# FanControl.net
KiCad netlist of a schematic drawn in Altium Designer
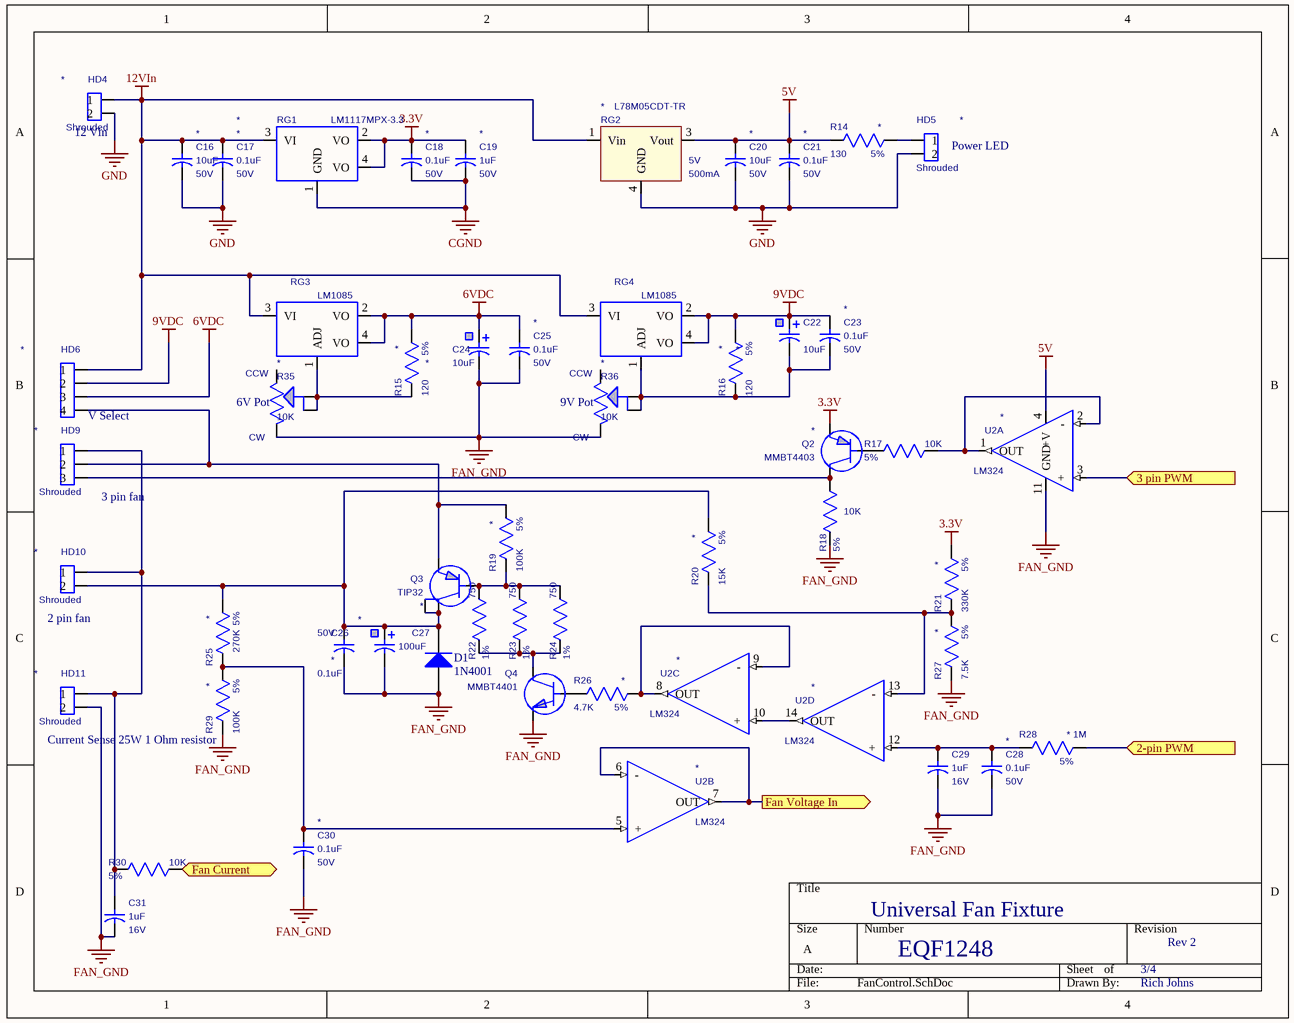
[diagram p0: FanControl.SchDoc]

(export (version "E")
  (design (tool "Eeschema 10.0.6"))
  (components
    (comp (ref "C16")
      (value "10uF")
      (footprint "1206")
      (fields
        (field (name "DNS") "*")
        (field (name "VOLTAGE") "50V")
        (field (name "TOLERANCE") "+/- 20%")
        (field (name "Comment") "CAP_NON_POLAR_SMT")
        (field (name "CHECKEDBY") "Sam Rhoufiry")
        (field (name "CREATEDBY") "Mike Tyger")
        (field (name "LASTUPDATEDBY") "Mike Tyger")
      )
      (libsource (lib "bome") (part "CAP_NON_POLAR_SMT"))
    )
    (comp (ref "C17")
      (value "0.1uF")
      (footprint "0603")
      (fields
        (field (name "DNS") "*")
        (field (name "VOLTAGE") "50V")
        (field (name "TOLERANCE") "+/- 20%")
        (field (name "Comment") "CAP_NON_POLAR_SMT")
        (field (name "CHECKEDBY") "Sam Rhoufiry")
        (field (name "CREATEDBY") "Mike Tyger")
        (field (name "LASTUPDATEDBY") "Mike Tyger")
      )
      (libsource (lib "bome") (part "CAP_NON_POLAR_SMT"))
    )
    (comp (ref "C18")
      (value "0.1uF")
      (footprint "0603")
      (fields
        (field (name "DNS") "*")
        (field (name "VOLTAGE") "50V")
        (field (name "TOLERANCE") "+/- 20%")
        (field (name "Comment") "CAP_NON_POLAR_SMT")
        (field (name "CHECKEDBY") "Sam Rhoufiry")
        (field (name "CREATEDBY") "Mike Tyger")
        (field (name "LASTUPDATEDBY") "Mike Tyger")
      )
      (libsource (lib "bome") (part "CAP_NON_POLAR_SMT"))
    )
    (comp (ref "C19")
      (value "1uF")
      (footprint "1812")
      (description "Capacitor, 1uF, 50V, Ceramic, Z5U, +/- 20%, Non-Polar, 1812, Kemet: C1812C105M5UACTU or equivalent")
      (fields
        (field (name "DNS") "*")
        (field (name "VOLTAGE") "50V")
        (field (name "TOLERANCE") "+/- 20%")
        (field (name "Comment") "CAP_NON_POLAR_SMT")
        (field (name "CHECKEDBY") "Sam Rhoufiry")
        (field (name "CREATEDBY") "Mike Tyger")
        (field (name "LASTUPDATEDBY") "Mike Tyger")
      )
      (libsource (lib "bome") (part "CAP_NON_POLAR_SMT"))
    )
    (comp (ref "C20")
      (value "10uF")
      (footprint "1206")
      (fields
        (field (name "DNS") "*")
        (field (name "VOLTAGE") "50V")
        (field (name "TOLERANCE") "+/- 20%")
        (field (name "Comment") "CAP_NON_POLAR_SMT")
        (field (name "CHECKEDBY") "Sam Rhoufiry")
        (field (name "CREATEDBY") "Mike Tyger")
        (field (name "LASTUPDATEDBY") "Mike Tyger")
      )
      (libsource (lib "bome") (part "CAP_NON_POLAR_SMT"))
    )
    (comp (ref "C21")
      (value "0.1uF")
      (footprint "0603")
      (fields
        (field (name "DNS") "*")
        (field (name "VOLTAGE") "50V")
        (field (name "TOLERANCE") "+/- 20%")
        (field (name "Comment") "CAP_NON_POLAR_SMT")
        (field (name "CHECKEDBY") "Sam Rhoufiry")
        (field (name "CREATEDBY") "Mike Tyger")
        (field (name "LASTUPDATEDBY") "Mike Tyger")
      )
      (libsource (lib "bome") (part "CAP_NON_POLAR_SMT"))
    )
    (comp (ref "C22")
      (value "10uF")
      (footprint "EIA3216-18")
      (fields
        (field (name "VOLTAGE") "16V")
        (field (name "TOLERANCE") "+/- 20%")
        (field (name "DNS") "*")
        (field (name "Comment") "10UF_TANT_16V")
        (field (name "CHECKEDBY") "B. Lyon")
      )
      (libsource (lib "bome") (part "10UF_TANT_16V"))
    )
    (comp (ref "C23")
      (value "0.1uF")
      (footprint "0603")
      (fields
        (field (name "DNS") "*")
        (field (name "VOLTAGE") "50V")
        (field (name "TOLERANCE") "+/- 20%")
        (field (name "Comment") "CAP_NON_POLAR_SMT")
        (field (name "CHECKEDBY") "Sam Rhoufiry")
        (field (name "CREATEDBY") "Mike Tyger")
        (field (name "LASTUPDATEDBY") "Mike Tyger")
      )
      (libsource (lib "bome") (part "CAP_NON_POLAR_SMT"))
    )
    (comp (ref "C24")
      (value "10uF")
      (footprint "EIA3216-18")
      (fields
        (field (name "VOLTAGE") "16V")
        (field (name "TOLERANCE") "+/- 20%")
        (field (name "DNS") "*")
        (field (name "Comment") "10UF_TANT_16V")
        (field (name "CHECKEDBY") "B. Lyon")
      )
      (libsource (lib "bome") (part "10UF_TANT_16V"))
    )
    (comp (ref "C25")
      (value "0.1uF")
      (footprint "0603")
      (fields
        (field (name "DNS") "*")
        (field (name "VOLTAGE") "50V")
        (field (name "TOLERANCE") "+/- 20%")
        (field (name "Comment") "CAP_NON_POLAR_SMT")
        (field (name "CHECKEDBY") "Sam Rhoufiry")
        (field (name "CREATEDBY") "Mike Tyger")
        (field (name "LASTUPDATEDBY") "Mike Tyger")
      )
      (libsource (lib "bome") (part "CAP_NON_POLAR_SMT"))
    )
    (comp (ref "C26")
      (value "100uF")
      (footprint "CAP_100RP42")
      (fields
        (field (name "DNS") "*")
        (field (name "VOLTAGE") "35V")
        (field (name "TOLERANCE") "+/- 20%")
        (field (name "Comment") "100UF_RP_35V_100")
        (field (name "CHECKEDBY") "A. Tyger")
      )
      (libsource (lib "bome") (part "100UF_RP_35V_100"))
    )
    (comp (ref "C27")
      (value "0.1uF")
      (footprint "0603")
      (fields
        (field (name "DNS") "*")
        (field (name "VOLTAGE") "50V")
        (field (name "TOLERANCE") "+/- 20%")
        (field (name "Comment") "CAP_NON_POLAR_SMT")
        (field (name "CHECKEDBY") "Sam Rhoufiry")
        (field (name "CREATEDBY") "Mike Tyger")
        (field (name "LASTUPDATEDBY") "Mike Tyger")
      )
      (libsource (lib "bome") (part "CAP_NON_POLAR_SMT"))
    )
    (comp (ref "C28")
      (value "0.1uF")
      (footprint "0603")
      (fields
        (field (name "DNS") "*")
        (field (name "VOLTAGE") "50V")
        (field (name "TOLERANCE") "+/- 20%")
        (field (name "Comment") "CAP_NON_POLAR_SMT")
        (field (name "CHECKEDBY") "Sam Rhoufiry")
        (field (name "CREATEDBY") "Mike Tyger")
        (field (name "LASTUPDATEDBY") "Mike Tyger")
      )
      (libsource (lib "bome") (part "CAP_NON_POLAR_SMT"))
    )
    (comp (ref "C29")
      (value "1uF")
      (footprint "0603")
      (fields
        (field (name "TOLERANCE") "+/- 10%")
        (field (name "VOLTAGE") "16V")
        (field (name "Comment") "1.0uF_0603_16V")
        (field (name "CHECKEDBY") "gdeguzman")
        (field (name "LASTUPDATEDBY") "Rui Zhang")
      )
      (libsource (lib "bome") (part "1.0uF_0603_16V"))
    )
    (comp (ref "C30")
      (value "0.1uF")
      (footprint "0603")
      (fields
        (field (name "DNS") "*")
        (field (name "VOLTAGE") "50V")
        (field (name "TOLERANCE") "+/- 20%")
        (field (name "Comment") "CAP_NON_POLAR_SMT")
        (field (name "CHECKEDBY") "Sam Rhoufiry")
        (field (name "CREATEDBY") "Mike Tyger")
        (field (name "LASTUPDATEDBY") "Mike Tyger")
      )
      (libsource (lib "bome") (part "CAP_NON_POLAR_SMT"))
    )
    (comp (ref "C31")
      (value "1uF")
      (footprint "0603")
      (fields
        (field (name "TOLERANCE") "+/- 10%")
        (field (name "VOLTAGE") "16V")
        (field (name "Comment") "1.0uF_0603_16V")
        (field (name "CHECKEDBY") "gdeguzman")
        (field (name "LASTUPDATEDBY") "Rui Zhang")
      )
      (libsource (lib "bome") (part "1.0uF_0603_16V"))
    )
    (comp (ref "D1")
      (value "1N4001")
      (footprint "DSO-C2/X3.3")
      (description "Default Diode")
      (fields (field (name "PUBLISHER") "Altium Limited"))
      (libsource (lib "Miscellaneous Devices") (part "Diode"))
    )
    (comp (ref "HD4")
      (value "HDR2PIN100SHRD")
      (footprint "HDR2PIN100SHRD")
      (description "Header, 0.100 in., 2 Pins, Shrouded, AMP: 644486-2")
      (fields
        (field (name "DNS") "*")
        (field (name "HEADERTYPE") "Shrouded")
        (field (name "CHECKEDBY") "*")
        (field (name "LASTUPDATEDBY") "Mike Tyger")
      )
      (libsource (lib "bome") (part "HDR2PIN100SHRD"))
    )
    (comp (ref "HD5")
      (value "HDR2PIN100SHRD")
      (footprint "HDR2PIN100SHRD")
      (description "Header, 0.100 in., 2 Pins, Shrouded, AMP: 644486-2")
      (fields
        (field (name "DNS") "*")
        (field (name "HEADERTYPE") "Shrouded")
        (field (name "CHECKEDBY") "*")
        (field (name "LASTUPDATEDBY") "Mike Tyger")
      )
      (libsource (lib "bome") (part "HDR2PIN100SHRD"))
    )
    (comp (ref "HD6")
      (value "HDR4PIN100SHRD")
      (footprint "HDR4PIN100SHRD")
      (description "Header, 0.100 in., 4 pin Pins, Shrouded, AMP: 644486-4")
      (fields (field (name "DNS") "*") (field (name "CHECKEDBY") "Michael Angeli"))
      (libsource (lib "bome") (part "HDR4PIN100SHRD"))
    )
    (comp (ref "HD9")
      (value "HDR3PIN100SHRD")
      (footprint "HDR3PIN100SHRD")
      (description "Header, 0.100 in., 3 pin Pins, Shrouded, AMP: 644486-3")
      (fields
        (field (name "DNS") "*")
        (field (name "HEADERTYPE") "Shrouded")
        (field (name "CHECKEDBY") "Grunt Mcfunkwhistle")
      )
      (libsource (lib "bome") (part "HDR3PIN100SHRD"))
    )
    (comp (ref "HD10")
      (value "HDR2PIN100SHRD")
      (footprint "HDR2PIN100SHRD")
      (description "Header, 0.100 in., 2 Pins, Shrouded, AMP: 644486-2")
      (fields
        (field (name "DNS") "*")
        (field (name "HEADERTYPE") "Shrouded")
        (field (name "CHECKEDBY") "*")
        (field (name "LASTUPDATEDBY") "Mike Tyger")
      )
      (libsource (lib "bome") (part "HDR2PIN100SHRD"))
    )
    (comp (ref "HD11")
      (value "HDR2PIN100SHRD")
      (footprint "HDR2PIN100SHRD")
      (description "Header, 0.100 in., 2 Pins, Shrouded, AMP: 644486-2")
      (fields
        (field (name "DNS") "*")
        (field (name "HEADERTYPE") "Shrouded")
        (field (name "CHECKEDBY") "*")
        (field (name "LASTUPDATEDBY") "Mike Tyger")
      )
      (libsource (lib "bome") (part "HDR2PIN100SHRD"))
    )
    (comp (ref "Q2")
      (value "MMBT4403")
      (footprint "SOT23-3")
      (description "Transistor, MMBT4403, 40V, SOT23-3, PNP, Transistor, On Semi: MMBT4403LT1")
      (fields
        (field (name "DNS") "*")
        (field (name "VOLTAGE") "40V")
        (field (name "Comment") "PNP_TRANSISTOR")
        (field (name "CHECKEDBY") "gdeguzman")
        (field (name "LASTUPDATEDBY") "Mike Tyger")
      )
      (libsource (lib "bome") (part "PNP_TRANSISTOR"))
    )
    (comp (ref "Q3")
      (value "TIP32")
      (footprint "TO-220-NORMAL")
      (description "Transistor, TIP32, 40V, TO-220, 3A, PNP, Any")
      (fields (field (name "VOLTAGE") "40V") (field (name "DNS") "*") (field (name "CHECKEDBY") "B. Lyon"))
      (libsource (lib "bome") (part "TIP32"))
    )
    (comp (ref "Q4")
      (value "MMBT4401")
      (footprint "SOT23-3")
      (description "Transistor, MMBT4401, 40V, SOT23, 500mA, 3, NPN, Transistor, On Semi: MMBT4401LT1")
      (fields
        (field (name "VOLTAGE") "40V")
        (field (name "Comment") "2N4401_SOT23")
        (field (name "CHECKEDBY") "gdeguzman")
        (field (name "LASTUPDATEDBY") "Mike Tyger")
      )
      (libsource (lib "bome") (part "2N4401_SOT23"))
    )
    (comp (ref "R14")
      (value "130")
      (footprint "RC0603REFLOW-IPC")
      (description "Resistor, 130, ThickFilm, 5%, 0603, 1/10W, Any")
      (fields
        (field (name "DNS") "*")
        (field (name "TOLERANCE") "5%")
        (field (name "Comment") "R0603REFLOW_5%")
        (field (name "CHECKEDBY") "Michael Angeli")
      )
      (libsource (lib "bome") (part "R0603REFLOW_5%"))
    )
    (comp (ref "R15")
      (value "120")
      (footprint "RC0603REFLOW-IPC")
      (description "Resistor, 120, ThickFilm, 5%, 0603, 1/10W, Any")
      (fields
        (field (name "DNS") "*")
        (field (name "TOLERANCE") "5%")
        (field (name "Comment") "R0603REFLOW_5%")
        (field (name "CHECKEDBY") "Michael Angeli")
      )
      (libsource (lib "bome") (part "R0603REFLOW_5%"))
    )
    (comp (ref "R16")
      (value "120")
      (footprint "RC0603REFLOW-IPC")
      (description "Resistor, 120, ThickFilm, 5%, 0603, 1/10W, Any")
      (fields
        (field (name "DNS") "*")
        (field (name "TOLERANCE") "5%")
        (field (name "Comment") "R0603REFLOW_5%")
        (field (name "CHECKEDBY") "Michael Angeli")
      )
      (libsource (lib "bome") (part "R0603REFLOW_5%"))
    )
    (comp (ref "R17")
      (value "10K")
      (footprint "0603")
      (description "Resistor, 10K, ThickFilm, 5%, 0603, 1/10W, 2, Any")
      (fields
        (field (name "TOLERANCE") "5%")
        (field (name "Comment") "Resistor_0603_5%")
        (field (name "CHECKEDBY") "Joe Diffie")
        (field (name "LASTUPDATEDBY") "Rui Zhang")
      )
      (libsource (lib "bome") (part "Resistor_0603_5%"))
    )
    (comp (ref "R18")
      (value "10K")
      (footprint "0603")
      (description "Resistor, 10K, ThickFilm, 5%, 0603, 1/10W, 2, Any")
      (fields
        (field (name "TOLERANCE") "5%")
        (field (name "Comment") "Resistor_0603_5%")
        (field (name "CHECKEDBY") "Joe Diffie")
        (field (name "LASTUPDATEDBY") "Rui Zhang")
      )
      (libsource (lib "bome") (part "Resistor_0603_5%"))
    )
    (comp (ref "R19")
      (value "100K")
      (footprint "RC0603REFLOW-IPC")
      (description "Resistor, 100K, ThickFilm, 5%, 0603, 1/10W, Any")
      (fields
        (field (name "DNS") "*")
        (field (name "TOLERANCE") "5%")
        (field (name "Comment") "R0603REFLOW_5%")
        (field (name "CHECKEDBY") "Michael Angeli")
      )
      (libsource (lib "bome") (part "R0603REFLOW_5%"))
    )
    (comp (ref "R20")
      (value "15K")
      (footprint "RC0603REFLOW-IPC")
      (description "Resistor, 15K, ThickFilm, 5%, 0603, 1/10W, Any")
      (fields
        (field (name "DNS") "*")
        (field (name "TOLERANCE") "5%")
        (field (name "Comment") "R0603REFLOW_5%")
        (field (name "CHECKEDBY") "Michael Angeli")
      )
      (libsource (lib "bome") (part "R0603REFLOW_5%"))
    )
    (comp (ref "R21")
      (value "330K")
      (footprint "RC0603REFLOW-IPC")
      (description "Resistor, 330K, ThickFilm, 5%, 0603, 1/10W, Any")
      (fields
        (field (name "DNS") "*")
        (field (name "TOLERANCE") "5%")
        (field (name "Comment") "R0603REFLOW_5%")
        (field (name "CHECKEDBY") "Michael Angeli")
      )
      (libsource (lib "bome") (part "R0603REFLOW_5%"))
    )
    (comp (ref "R22")
      (value "750")
      (footprint "0603")
      (description "Resistor, 750, 1%, 0603, 1/10W, 2, Any")
      (fields
        (field (name "TOLERANCE") "1%")
        (field (name "Comment") "Resistor_0603_1%")
        (field (name "CHECKEDBY") "gdeguzman")
        (field (name "LASTUPDATEDBY") "Ben Hill")
      )
      (libsource (lib "bome") (part "Resistor_0603_1%"))
    )
    (comp (ref "R23")
      (value "750")
      (footprint "0603")
      (description "Resistor, 750, 1%, 0603, 1/10W, 2, Any")
      (fields
        (field (name "TOLERANCE") "1%")
        (field (name "Comment") "Resistor_0603_1%")
        (field (name "CHECKEDBY") "gdeguzman")
        (field (name "LASTUPDATEDBY") "Ben Hill")
      )
      (libsource (lib "bome") (part "Resistor_0603_1%"))
    )
    (comp (ref "R24")
      (value "750")
      (footprint "0603")
      (description "Resistor, 750, 1%, 0603, 1/10W, 2, Any")
      (fields
        (field (name "TOLERANCE") "1%")
        (field (name "Comment") "Resistor_0603_1%")
        (field (name "CHECKEDBY") "gdeguzman")
        (field (name "LASTUPDATEDBY") "Ben Hill")
      )
      (libsource (lib "bome") (part "Resistor_0603_1%"))
    )
    (comp (ref "R25")
      (value "270K")
      (footprint "RC0603REFLOW-IPC")
      (description "Resistor, 270K, ThickFilm, 5%, 0603, 1/10W, Any")
      (fields
        (field (name "DNS") "*")
        (field (name "TOLERANCE") "5%")
        (field (name "Comment") "R0603REFLOW_5%")
        (field (name "CHECKEDBY") "Michael Angeli")
      )
      (libsource (lib "bome") (part "R0603REFLOW_5%"))
    )
    (comp (ref "R26")
      (value "4.7K")
      (footprint "RC0603REFLOW-IPC")
      (description "Resistor, 4.7K, ThickFilm, 5%, 0603, 1/10W, Any")
      (fields
        (field (name "DNS") "*")
        (field (name "TOLERANCE") "5%")
        (field (name "Comment") "R0603REFLOW_5%")
        (field (name "CHECKEDBY") "Michael Angeli")
      )
      (libsource (lib "bome") (part "R0603REFLOW_5%"))
    )
    (comp (ref "R27")
      (value "7.5K")
      (footprint "RC0603REFLOW-IPC")
      (description "Resistor, 7.5K, ThickFilm, 5%, 0603, 1/10W, Any")
      (fields
        (field (name "DNS") "*")
        (field (name "TOLERANCE") "5%")
        (field (name "Comment") "R0603REFLOW_5%")
        (field (name "CHECKEDBY") "Michael Angeli")
      )
      (libsource (lib "bome") (part "R0603REFLOW_5%"))
    )
    (comp (ref "R28")
      (value "1M")
      (footprint "RC0603REFLOW-IPC")
      (description "Resistor, 1M, ThickFilm, 5%, 0603, 1/10W, Any")
      (fields
        (field (name "DNS") "*")
        (field (name "TOLERANCE") "5%")
        (field (name "Comment") "R0603REFLOW_5%")
        (field (name "CHECKEDBY") "Michael Angeli")
      )
      (libsource (lib "bome") (part "R0603REFLOW_5%"))
    )
    (comp (ref "R29")
      (value "100K")
      (footprint "RC0603REFLOW-IPC")
      (description "Resistor, 100K, ThickFilm, 5%, 0603, 1/10W, Any")
      (fields
        (field (name "DNS") "*")
        (field (name "TOLERANCE") "5%")
        (field (name "Comment") "R0603REFLOW_5%")
        (field (name "CHECKEDBY") "Michael Angeli")
      )
      (libsource (lib "bome") (part "R0603REFLOW_5%"))
    )
    (comp (ref "R30")
      (value "10K")
      (footprint "0603")
      (description "Resistor, 10K, ThickFilm, 5%, 0603, 1/10W, 2, Any")
      (fields
        (field (name "TOLERANCE") "5%")
        (field (name "Comment") "Resistor_0603_5%")
        (field (name "CHECKEDBY") "Joe Diffie")
        (field (name "LASTUPDATEDBY") "Rui Zhang")
      )
      (libsource (lib "bome") (part "Resistor_0603_5%"))
    )
    (comp (ref "R35")
      (value "10K")
      (footprint "6MM POT")
      (description "Resistor, 10K, Carbon, 20%, 0.2 in X 0.1 in or 0.2 in X 0.2 in, 0.1W, Panasonic: EVN-D8AA03B14")
      (fields
        (field (name "TOLERANCE") "20%")
        (field (name "DNS") "*")
        (field (name "Comment") "POT 6MM 10K")
        (field (name "CHECKEDBY") "B. Lyon")
      )
      (libsource (lib "bome") (part "POT 6MM 10K"))
    )
    (comp (ref "R36")
      (value "10K")
      (footprint "6MM POT")
      (description "Resistor, 10K, Carbon, 20%, 0.2 in X 0.1 in or 0.2 in X 0.2 in, 0.1W, Panasonic: EVN-D8AA03B14")
      (fields
        (field (name "TOLERANCE") "20%")
        (field (name "DNS") "*")
        (field (name "Comment") "POT 6MM 10K")
        (field (name "CHECKEDBY") "B. Lyon")
      )
      (libsource (lib "bome") (part "POT 6MM 10K"))
    )
    (comp (ref "RG1")
      (value "LM1117MPX-3.3")
      (footprint "SOT-223")
      (description "Regulator, LM1117MPX-3.3, 3.3V, SOT223, 800mA, 4, LDO, National: LM117MPX-3.3")
      (fields
        (field (name "VOLTAGE") "3.3V")
        (field (name "DNS") "*")
        (field (name "Comment") "LM1117SPX-3.3_SOT223")
        (field (name "CHECKEDBY") "gdeguzman")
        (field (name "LASTUPDATEDBY") "Rui Zhang")
      )
      (libsource (lib "bome") (part "LM1117SPX-3.3_SOT223"))
    )
    (comp (ref "RG2")
      (value "L78M05CDT-TR")
      (footprint "DPAK")
      (description "Regulator, L78M05CDT-TR, 5V, DPAK, 500mA, Linear, ST: L78M05CDT-TR or equivalent")
      (fields
        (field (name "VOLTAGE") "5V")
        (field (name "DNS") "*")
        (field (name "AMPERAGE") "500mA")
        (field (name "Comment") "REGULATOR_DPAK")
        (field (name "CHECKEDBY") "B. Lyon")
        (field (name "CREATEDBY") "Mike Tyger")
        (field (name "LASTUPDATEDBY") "Mike Tyger")
      )
      (libsource (lib "bome") (part "REGULATOR_DPAK"))
    )
    (comp (ref "RG3")
      (value "LM1085")
      (footprint "TO-220-NORMAL")
      (description "Regulator, LM1085, Adjustable, TO-220, 3A, LDO, Texas Instruments")
      (fields
        (field (name "VOLTAGE") "Adjustable")
        (field (name "Comment") "LM1085_TO220")
        (field (name "CREATEDBY") "Rui Zhang")
        (field (name "LASTUPDATEDBY") "Rui Zhang")
      )
      (libsource (lib "bome") (part "LM1085_TO220"))
    )
    (comp (ref "RG4")
      (value "LM1085")
      (footprint "TO-220-NORMAL")
      (description "Regulator, LM1085, Adjustable, TO-220, 3A, LDO, Texas Instruments")
      (fields
        (field (name "VOLTAGE") "Adjustable")
        (field (name "Comment") "LM1085_TO220")
        (field (name "CREATEDBY") "Rui Zhang")
        (field (name "LASTUPDATEDBY") "Rui Zhang")
      )
      (libsource (lib "bome") (part "LM1085_TO220"))
    )
    (comp (ref "U2")
      (value "LM324")
      (footprint "SOIC14REFLOW-IPC")
      (description "IC, LM324, SOIC, 14 pin, Op-Amp, National Semiconductor")
      (fields
        (field (name "DNS") "*")
        (field (name "Comment") "LM324_SOIC14")
        (field (name "CHECKEDBY") "B. Lyon")
      )
      (libsource (lib "bome") (part "LM324_SOIC14"))
    )
  )
  (nets
    (net (code "1") (name "/2-pin PWM") (class "Default")
      (node (ref "R28") (pin "1") (pinfunction "pin1_1") (pintype "passive"))
    )
    (net (code "2") (name "/3 pin PWM") (class "Default")
      (node (ref "U2") (pin "3") (pinfunction "+_3") (pintype "input"))
    )
    (net (code "3") (name "/Fan Current") (class "Default")
      (node (ref "R30") (pin "1") (pinfunction "pin1_1") (pintype "passive"))
    )
    (net (code "4") (name "/Fan Voltage In") (class "Default")
      (node (ref "U2") (pin "6") (pinfunction "-_6") (pintype "input"))
      (node (ref "U2") (pin "7") (pinfunction "OUT_7") (pintype "output"))
    )
    (net (code "5") (name "3.3V") (class "Default")
      (node (ref "C18") (pin "1") (pinfunction "pin1_1") (pintype "passive"))
      (node (ref "C19") (pin "1") (pinfunction "pin1_1") (pintype "passive"))
      (node (ref "Q2") (pin "2") (pinfunction "emitter_2") (pintype "passive"))
      (node (ref "R21") (pin "1") (pinfunction "pin1_1") (pintype "passive"))
      (node (ref "RG1") (pin "2") (pinfunction "VO_2") (pintype "passive"))
      (node (ref "RG1") (pin "4") (pinfunction "VO_4") (pintype "passive"))
    )
    (net (code "6") (name "5V") (class "Default")
      (node (ref "C20") (pin "1") (pinfunction "pin1_1") (pintype "passive"))
      (node (ref "C21") (pin "1") (pinfunction "pin1_1") (pintype "passive"))
      (node (ref "R14") (pin "2") (pinfunction "pin2_2") (pintype "passive"))
      (node (ref "RG2") (pin "3") (pinfunction "Vout_3") (pintype "passive"))
      (node (ref "U2") (pin "4") (pinfunction "+V_4") (pintype "power_in"))
    )
    (net (code "7") (name "6VDC") (class "Default")
      (node (ref "C24") (pin "1") (pinfunction "+_1") (pintype "passive"))
      (node (ref "C25") (pin "1") (pinfunction "pin1_1") (pintype "passive"))
      (node (ref "HD6") (pin "3") (pinfunction "3_3") (pintype "passive"))
      (node (ref "R15") (pin "1") (pinfunction "pin1_1") (pintype "passive"))
      (node (ref "RG3") (pin "2") (pinfunction "VO_2") (pintype "passive"))
      (node (ref "RG3") (pin "4") (pinfunction "VO_4") (pintype "passive"))
    )
    (net (code "8") (name "9VDC") (class "Default")
      (node (ref "C22") (pin "1") (pinfunction "+_1") (pintype "passive"))
      (node (ref "C23") (pin "1") (pinfunction "pin1_1") (pintype "passive"))
      (node (ref "HD6") (pin "2") (pinfunction "2_2") (pintype "passive"))
      (node (ref "R16") (pin "1") (pinfunction "pin1_1") (pintype "passive"))
      (node (ref "RG4") (pin "2") (pinfunction "VO_2") (pintype "passive"))
      (node (ref "RG4") (pin "4") (pinfunction "VO_4") (pintype "passive"))
    )
    (net (code "9") (name "12VIn") (class "Default")
      (node (ref "C16") (pin "1") (pinfunction "pin1_1") (pintype "passive"))
      (node (ref "C17") (pin "1") (pinfunction "pin1_1") (pintype "passive"))
      (node (ref "HD4") (pin "1") (pinfunction "1_1") (pintype "passive"))
      (node (ref "HD6") (pin "1") (pinfunction "1_1") (pintype "passive"))
      (node (ref "RG1") (pin "3") (pinfunction "VI_3") (pintype "passive"))
      (node (ref "RG2") (pin "1") (pinfunction "Vin_1") (pintype "passive"))
      (node (ref "RG3") (pin "3") (pinfunction "VI_3") (pintype "passive"))
      (node (ref "RG4") (pin "3") (pinfunction "VI_3") (pintype "passive"))
    )
    (net (code "10") (name "CGND") (class "Default")
      (node (ref "C18") (pin "2") (pinfunction "pin2_2") (pintype "passive"))
      (node (ref "C19") (pin "2") (pinfunction "pin2_2") (pintype "passive"))
      (node (ref "RG1") (pin "1") (pinfunction "GND_1") (pintype "passive"))
    )
    (net (code "11") (name "FAN_GND") (class "Default")
      (node (ref "C24") (pin "2") (pinfunction "-_2") (pintype "passive"))
      (node (ref "C25") (pin "2") (pinfunction "pin2_2") (pintype "passive"))
      (node (ref "C26") (pin "2") (pinfunction "pin2_2") (pintype "passive"))
      (node (ref "C27") (pin "2") (pinfunction "pin2_2") (pintype "passive"))
      (node (ref "C28") (pin "2") (pinfunction "pin2_2") (pintype "passive"))
      (node (ref "C29") (pin "2") (pinfunction "pin2_2") (pintype "passive"))
      (node (ref "C30") (pin "2") (pinfunction "pin2_2") (pintype "passive"))
      (node (ref "C31") (pin "2") (pinfunction "pin2_2") (pintype "passive"))
      (node (ref "D1") (pin "1") (pinfunction "A_1") (pintype "passive"))
      (node (ref "HD11") (pin "2") (pinfunction "2_2") (pintype "passive"))
      (node (ref "Q4") (pin "2") (pinfunction "emitter_2") (pintype "passive"))
      (node (ref "R18") (pin "2") (pinfunction "pin2_2") (pintype "passive"))
      (node (ref "R27") (pin "2") (pinfunction "pin2_2") (pintype "passive"))
      (node (ref "R29") (pin "2") (pinfunction "pin2_2") (pintype "passive"))
      (node (ref "R35") (pin "4") (pinfunction "1_4") (pintype "passive"))
      (node (ref "R36") (pin "4") (pinfunction "1_4") (pintype "passive"))
      (node (ref "U2") (pin "11") (pinfunction "GND_11") (pintype "power_in"))
    )
    (net (code "12") (name "GND") (class "Default")
      (node (ref "C16") (pin "2") (pinfunction "pin2_2") (pintype "passive"))
      (node (ref "C17") (pin "2") (pinfunction "pin2_2") (pintype "passive"))
      (node (ref "C20") (pin "2") (pinfunction "pin2_2") (pintype "passive"))
      (node (ref "C21") (pin "2") (pinfunction "pin2_2") (pintype "passive"))
      (node (ref "HD4") (pin "2") (pinfunction "2_2") (pintype "passive"))
      (node (ref "HD5") (pin "2") (pinfunction "2_2") (pintype "passive"))
      (node (ref "RG2") (pin "4") (pinfunction "GND_4") (pintype "passive"))
    )
    (net (code "13") (name "Net-(C22--)") (class "Default")
      (node (ref "C22") (pin "2") (pinfunction "-_2") (pintype "passive"))
      (node (ref "C23") (pin "2") (pinfunction "pin2_2") (pintype "passive"))
      (node (ref "R16") (pin "2") (pinfunction "pin2_2") (pintype "passive"))
      (node (ref "R36") (pin "2") (pinfunction "1_2") (pintype "passive"))
      (node (ref "R36") (pin "3") (pinfunction "1_3") (pintype "passive"))
      (node (ref "RG4") (pin "1") (pinfunction "ADJ_1") (pintype "passive"))
    )
    (net (code "14") (name "Net-(C26-pin1)") (class "Default")
      (node (ref "C26") (pin "1") (pinfunction "pin1_1") (pintype "passive"))
      (node (ref "C27") (pin "1") (pinfunction "pin1_1") (pintype "passive"))
      (node (ref "D1") (pin "2") (pinfunction "K_2") (pintype "passive"))
      (node (ref "HD10") (pin "2") (pinfunction "2_2") (pintype "passive"))
      (node (ref "Q3") (pin "2") (pinfunction "C_2") (pintype "passive"))
      (node (ref "Q3") (pin "4") (pinfunction "C_4") (pintype "passive"))
      (node (ref "R20") (pin "1") (pinfunction "pin1_1") (pintype "passive"))
      (node (ref "R25") (pin "1") (pinfunction "pin1_1") (pintype "passive"))
    )
    (net (code "15") (name "Net-(C28-pin1)") (class "Default")
      (node (ref "C28") (pin "1") (pinfunction "pin1_1") (pintype "passive"))
      (node (ref "C29") (pin "1") (pinfunction "pin1_1") (pintype "passive"))
      (node (ref "R28") (pin "2") (pinfunction "pin2_2") (pintype "passive"))
      (node (ref "U2") (pin "12") (pinfunction "+_12") (pintype "input"))
    )
    (net (code "16") (name "Net-(C30-pin1)") (class "Default")
      (node (ref "C30") (pin "1") (pinfunction "pin1_1") (pintype "passive"))
      (node (ref "R25") (pin "2") (pinfunction "pin2_2") (pintype "passive"))
      (node (ref "R29") (pin "1") (pinfunction "pin1_1") (pintype "passive"))
      (node (ref "U2") (pin "5") (pinfunction "+_5") (pintype "input"))
    )
    (net (code "17") (name "Net-(C31-pin1)") (class "Default")
      (node (ref "C31") (pin "1") (pinfunction "pin1_1") (pintype "passive"))
      (node (ref "HD10") (pin "1") (pinfunction "1_1") (pintype "passive"))
      (node (ref "HD11") (pin "1") (pinfunction "1_1") (pintype "passive"))
      (node (ref "HD9") (pin "1") (pinfunction "1_1") (pintype "passive"))
      (node (ref "R30") (pin "2") (pinfunction "pin2_2") (pintype "passive"))
    )
    (net (code "18") (name "Net-(Q2-base)") (class "Default")
      (node (ref "Q2") (pin "1") (pinfunction "base_1") (pintype "passive"))
      (node (ref "R17") (pin "2") (pinfunction "pin2_2") (pintype "passive"))
    )
    (net (code "19") (name "Net-(Q2-collector)") (class "Default")
      (node (ref "HD9") (pin "3") (pinfunction "3_3") (pintype "passive"))
      (node (ref "Q2") (pin "3") (pinfunction "collector_3") (pintype "passive"))
      (node (ref "R18") (pin "1") (pinfunction "pin1_1") (pintype "passive"))
    )
    (net (code "20") (name "Net-(Q3-B)") (class "Default")
      (node (ref "Q3") (pin "1") (pinfunction "B_1") (pintype "passive"))
      (node (ref "R19") (pin "2") (pinfunction "pin2_2") (pintype "passive"))
      (node (ref "R22") (pin "1") (pinfunction "pin1_1") (pintype "passive"))
      (node (ref "R23") (pin "1") (pinfunction "pin1_1") (pintype "passive"))
      (node (ref "R24") (pin "1") (pinfunction "pin1_1") (pintype "passive"))
    )
    (net (code "21") (name "Net-(Q3-E)") (class "Default")
      (node (ref "HD6") (pin "4") (pinfunction "4_4") (pintype "passive"))
      (node (ref "HD9") (pin "2") (pinfunction "2_2") (pintype "passive"))
      (node (ref "Q3") (pin "3") (pinfunction "E_3") (pintype "passive"))
      (node (ref "R19") (pin "1") (pinfunction "pin1_1") (pintype "passive"))
    )
    (net (code "22") (name "Net-(Q4-base)") (class "Default")
      (node (ref "Q4") (pin "1") (pinfunction "base_1") (pintype "passive"))
      (node (ref "R26") (pin "2") (pinfunction "pin2_2") (pintype "passive"))
    )
    (net (code "23") (name "Net-(Q4-collector)") (class "Default")
      (node (ref "Q4") (pin "3") (pinfunction "collector_3") (pintype "passive"))
      (node (ref "R22") (pin "2") (pinfunction "pin2_2") (pintype "passive"))
      (node (ref "R23") (pin "2") (pinfunction "pin2_2") (pintype "passive"))
      (node (ref "R24") (pin "2") (pinfunction "pin2_2") (pintype "passive"))
    )
    (net (code "24") (name "Net-(R14-pin1)") (class "Default")
      (node (ref "HD5") (pin "1") (pinfunction "1_1") (pintype "passive"))
      (node (ref "R14") (pin "1") (pinfunction "pin1_1") (pintype "passive"))
    )
    (net (code "25") (name "Net-(R15-pin2)") (class "Default")
      (node (ref "R15") (pin "2") (pinfunction "pin2_2") (pintype "passive"))
      (node (ref "R35") (pin "2") (pinfunction "1_2") (pintype "passive"))
      (node (ref "R35") (pin "3") (pinfunction "1_3") (pintype "passive"))
      (node (ref "RG3") (pin "1") (pinfunction "ADJ_1") (pintype "passive"))
    )
    (net (code "26") (name "Net-(R17-pin1)") (class "Default")
      (node (ref "R17") (pin "1") (pinfunction "pin1_1") (pintype "passive"))
      (node (ref "U2") (pin "1") (pinfunction "OUT_1") (pintype "output"))
      (node (ref "U2") (pin "2") (pinfunction "-_2") (pintype "input"))
    )
    (net (code "27") (name "Net-(R20-pin2)") (class "Default")
      (node (ref "R20") (pin "2") (pinfunction "pin2_2") (pintype "passive"))
      (node (ref "R21") (pin "2") (pinfunction "pin2_2") (pintype "passive"))
      (node (ref "R27") (pin "1") (pinfunction "pin1_1") (pintype "passive"))
      (node (ref "U2") (pin "13") (pinfunction "-_13") (pintype "input"))
    )
    (net (code "28") (name "Net-(R26-pin1)") (class "Default")
      (node (ref "R26") (pin "1") (pinfunction "pin1_1") (pintype "passive"))
      (node (ref "U2") (pin "8") (pinfunction "OUT_8") (pintype "output"))
      (node (ref "U2") (pin "9") (pinfunction "-_9") (pintype "input"))
    )
    (net (code "29") (name "Net-(U2C-+)") (class "Default")
      (node (ref "U2") (pin "10") (pinfunction "+_10") (pintype "input"))
      (node (ref "U2") (pin "14") (pinfunction "OUT_14") (pintype "output"))
    )
    (net (code "30") (name "unconnected-(HD4-Pad3)") (class "Default")
      (node (ref "HD4") (pin "3") (pintype "passive"))
    )
    (net (code "31") (name "unconnected-(HD5-Pad3)") (class "Default")
      (node (ref "HD5") (pin "3") (pintype "passive"))
    )
    (net (code "32") (name "unconnected-(HD6-Pad5)") (class "Default")
      (node (ref "HD6") (pin "5") (pintype "passive"))
    )
    (net (code "33") (name "unconnected-(HD9-Pad4)") (class "Default")
      (node (ref "HD9") (pin "4") (pintype "passive"))
    )
    (net (code "34") (name "unconnected-(HD10-Pad3)") (class "Default")
      (node (ref "HD10") (pin "3") (pintype "passive"))
    )
    (net (code "35") (name "unconnected-(HD11-Pad3)") (class "Default")
      (node (ref "HD11") (pin "3") (pintype "passive"))
    )
    (net (code "36") (name "unconnected-(R35-Pad1)") (class "Default")
      (node (ref "R35") (pin "1") (pinfunction "1_1") (pintype "passive"))
    )
    (net (code "37") (name "unconnected-(R36-Pad1)") (class "Default")
      (node (ref "R36") (pin "1") (pinfunction "1_1") (pintype "passive"))
    )
    (net (code "38") (name "unconnected-(RG2-GND-Pad2)") (class "Default")
      (node (ref "RG2") (pin "2") (pinfunction "GND_2") (pintype "passive"))
    )
  )
)
